# 1_PowerStage12To5.net
KiCad netlist of a schematic drawn in Altium Designer
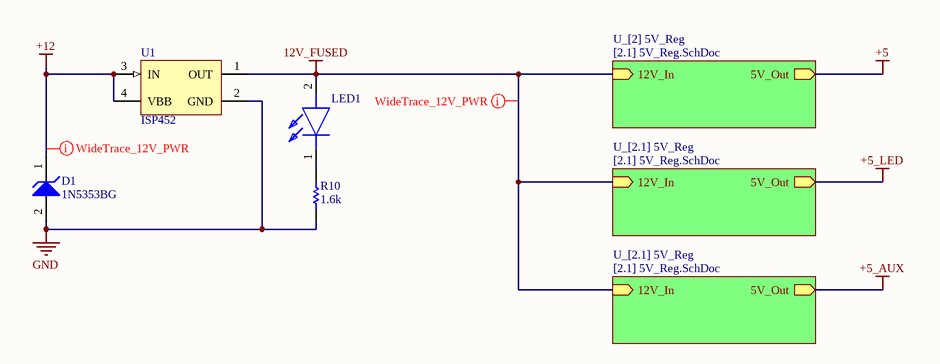
[diagram p0: [1] PowerStage12To5.SchDoc]

(export (version "E")
  (design (tool "Eeschema 10.0.6"))
  (components
    (comp (ref "D1")
      (value "1N5353BG")
      (footprint "ONSC-SURMETIC40-2-017AA-01")
      (description "5 W Zener Voltage Regulator, 2-Pin Surmetic(TM) 40, Pb-Free, Bulk Box")
      (fields (field (name "MANUFACTURER") "On Semiconductor"))
      (libsource (lib "Altium Content Vault") (part "ONSC-K1A2-2"))
    )
    (comp (ref "LED1")
      (value "150060GS75000")
      (footprint "SamacSys:LEDC1608X80N")
      (description "LED")
      (fields (field (name "MOUSER PART NUMBER") "710-150060GS75000"))
      (libsource (lib "*") (part "150060GS75000"))
    )
    (comp (ref "R10")
      (value "1.6k")
      (footprint "RESC0603(1608)_L")
      (description "2R94 0.1W 1% 0603 (1608 Metric)  SMD")
      (fields (field (name "POWER") "0.1 W") (field (name "TOLERANCE") "1 %"))
      (libsource (lib "Altium Content Vault") (part "RES"))
    )
    (comp (ref "U1")
      (value "ISP452")
      (footprint "INF-SOT223_L")
      (fields (field (name "MANUFACTURER") "Infineon"))
      (libsource (lib "Altium Content Vault") (part "INF-ISP452-SOT223-4"))
    )
  )
  (nets
    (net (code "4") (name "+12") (class "Default")
      (node (ref "D1") (pin "1") (pinfunction "K_1") (pintype "passive"))
      (node (ref "U1") (pin "3") (pinfunction "IN_3") (pintype "input"))
      (node (ref "U1") (pin "4") (pinfunction "VBB_4") (pintype "power_in"))
    )
    (net (code "5") (name "12V_FUSED") (class "Default")
      (node (ref "LED1") (pin "2") (pinfunction "A_2") (pintype "passive"))
      (node (ref "U1") (pin "1") (pinfunction "OUT_1") (pintype "power_in"))
    )
    (net (code "6") (name "GND") (class "Default")
      (node (ref "D1") (pin "2") (pinfunction "A_2") (pintype "passive"))
      (node (ref "R10") (pin "1") (pinfunction "1_1") (pintype "passive"))
      (node (ref "U1") (pin "2") (pinfunction "GND_2") (pintype "power_in"))
    )
    (net (code "7") (name "Net-(LED1-K)") (class "Default")
      (node (ref "LED1") (pin "1") (pinfunction "K_1") (pintype "passive"))
      (node (ref "R10") (pin "2") (pinfunction "2_2") (pintype "passive"))
    )
  )
)
